# 1-Schematic_New_Project.net
KiCad netlist of a schematic drawn in EasyEDA
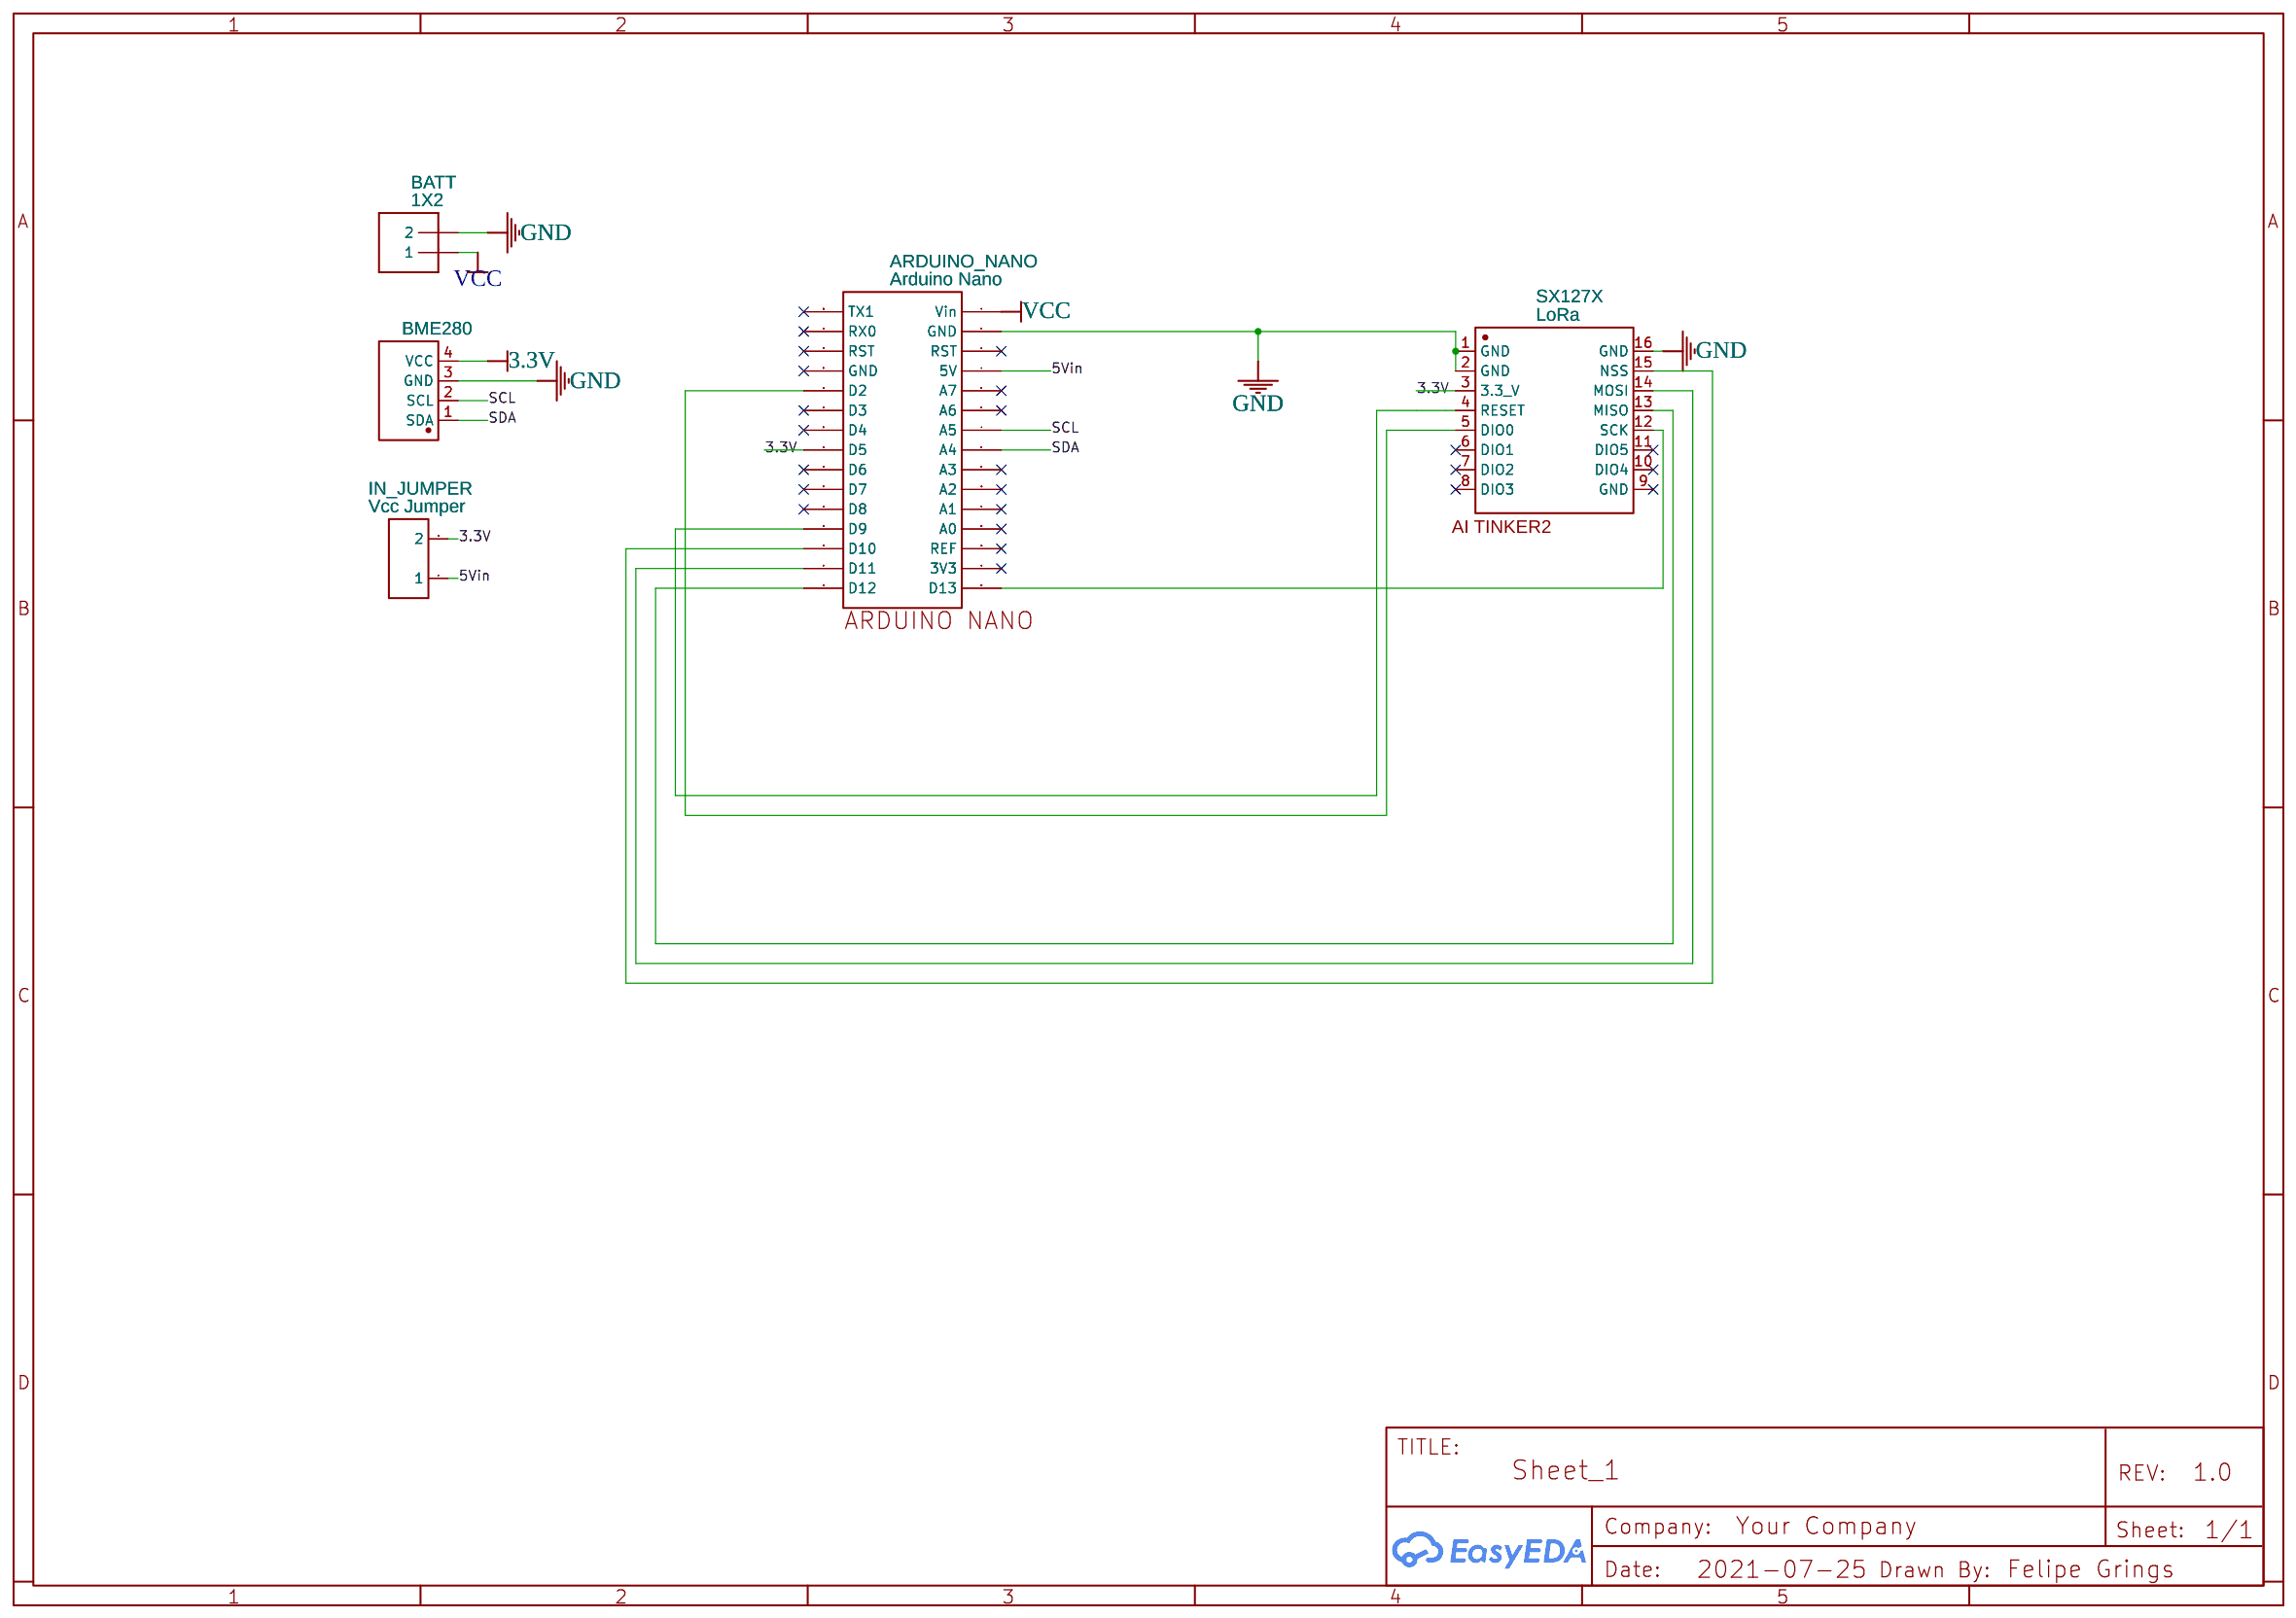
[diagram p0: schematic sheet]

(export (version "E")
  (design (tool "Eeschema 10.0.6"))
  (components
    (comp (ref "ARDUINO_NANO") (value "Arduino Nano") (libsource (lib "") (part "Arduino Nano")))
    (comp (ref "BATT") (value "1X2") (libsource (lib "") (part "1X2")))
    (comp (ref "IN_JUMPER")
      (value "Vcc Jumper")
      (fields (field (name "BOM_Manufacturer Part") "826629-2") (field (name "BOM_Supplier Part") "C86471"))
      (libsource (lib "") (part "Header-Male-2.54_1x2"))
    )
    (comp (ref "SDA") (value "BME280") (libsource (lib "") (part "GYBMEP")))
    (comp (ref "SX127X")
      (value "LoRa")
      (fields (field (name "BOM_Manufacturer Part") "SX1278") (field (name "BOM_Supplier Part") "C87473"))
      (libsource (lib "") (part "LoRa"))
    )
  )
  (nets
    (net (code "1") (name "/5Vin") (class "Default")
      (node (ref "ARDUINO_NANO") (pin "4") (pinfunction "5V_4") (pintype "unspecified"))
      (node (ref "IN_JUMPER") (pin "1") (pinfunction "1_1") (pintype "unspecified"))
    )
    (net (code "2") (name "/SCL") (class "Default")
      (node (ref "ARDUINO_NANO") (pin "7") (pinfunction "A5_7") (pintype "unspecified"))
      (node (ref "SDA") (pin "2") (pinfunction "SCL_2") (pintype "unspecified"))
    )
    (net (code "3") (name "/SDA") (class "Default")
      (node (ref "ARDUINO_NANO") (pin "8") (pinfunction "A4_8") (pintype "unspecified"))
      (node (ref "SDA") (pin "1") (pinfunction "SDA_1") (pintype "unspecified"))
    )
    (net (code "4") (name "3.3V") (class "Default")
      (node (ref "ARDUINO_NANO") (pin "23") (pinfunction "D5_23") (pintype "unspecified"))
      (node (ref "IN_JUMPER") (pin "2") (pinfunction "2_2") (pintype "unspecified"))
      (node (ref "SDA") (pin "4") (pinfunction "VCC_4") (pintype "unspecified"))
      (node (ref "SX127X") (pin "3") (pinfunction "3.3_V_3") (pintype "unspecified"))
    )
    (net (code "5") (name "GND") (class "Default")
      (node (ref "ARDUINO_NANO") (pin "2") (pinfunction "GND_2") (pintype "unspecified"))
      (node (ref "BATT") (pin "2") (pinfunction "2_2") (pintype "unspecified"))
      (node (ref "SDA") (pin "3") (pinfunction "GND_3") (pintype "unspecified"))
      (node (ref "SX127X") (pin "1") (pinfunction "GND_1") (pintype "unspecified"))
      (node (ref "SX127X") (pin "16") (pinfunction "GND_16") (pintype "unspecified"))
      (node (ref "SX127X") (pin "2") (pinfunction "GND_2") (pintype "unspecified"))
    )
    (net (code "6") (name "Net-(ARDUINO_NANO-D2)") (class "Default")
      (node (ref "ARDUINO_NANO") (pin "26") (pinfunction "D2_26") (pintype "unspecified"))
      (node (ref "SX127X") (pin "5") (pinfunction "DIO0_5") (pintype "unspecified"))
    )
    (net (code "7") (name "Net-(ARDUINO_NANO-D9)") (class "Default")
      (node (ref "ARDUINO_NANO") (pin "19") (pinfunction "D9_19") (pintype "unspecified"))
      (node (ref "SX127X") (pin "4") (pinfunction "RESET_4") (pintype "unspecified"))
    )
    (net (code "8") (name "Net-(ARDUINO_NANO-D10)") (class "Default")
      (node (ref "ARDUINO_NANO") (pin "18") (pinfunction "D10_18") (pintype "unspecified"))
      (node (ref "SX127X") (pin "15") (pinfunction "NSS_15") (pintype "unspecified"))
    )
    (net (code "9") (name "Net-(ARDUINO_NANO-D11)") (class "Default")
      (node (ref "ARDUINO_NANO") (pin "17") (pinfunction "D11_17") (pintype "unspecified"))
      (node (ref "SX127X") (pin "14") (pinfunction "MOSI_14") (pintype "unspecified"))
    )
    (net (code "10") (name "Net-(ARDUINO_NANO-D12)") (class "Default")
      (node (ref "ARDUINO_NANO") (pin "16") (pinfunction "D12_16") (pintype "unspecified"))
      (node (ref "SX127X") (pin "13") (pinfunction "MISO_13") (pintype "unspecified"))
    )
    (net (code "11") (name "Net-(ARDUINO_NANO-D13)") (class "Default")
      (node (ref "ARDUINO_NANO") (pin "15") (pinfunction "D13_15") (pintype "unspecified"))
      (node (ref "SX127X") (pin "12") (pinfunction "SCK_12") (pintype "unspecified"))
    )
    (net (code "12") (name "VCC") (class "Default")
      (node (ref "ARDUINO_NANO") (pin "1") (pinfunction "Vin_1") (pintype "unspecified"))
      (node (ref "BATT") (pin "1") (pinfunction "1_1") (pintype "unspecified"))
    )
    (net (code "13") (name "unconnected-(ARDUINO_NANO-3V3-Pad14)") (class "Default")
      (node (ref "ARDUINO_NANO") (pin "14") (pinfunction "3V3_14") (pintype "unspecified+no_connect"))
    )
    (net (code "14") (name "unconnected-(ARDUINO_NANO-A0-Pad12)") (class "Default")
      (node (ref "ARDUINO_NANO") (pin "12") (pinfunction "A0_12") (pintype "unspecified+no_connect"))
    )
    (net (code "15") (name "unconnected-(ARDUINO_NANO-A1-Pad11)") (class "Default")
      (node (ref "ARDUINO_NANO") (pin "11") (pinfunction "A1_11") (pintype "unspecified+no_connect"))
    )
    (net (code "16") (name "unconnected-(ARDUINO_NANO-A2-Pad10)") (class "Default")
      (node (ref "ARDUINO_NANO") (pin "10") (pinfunction "A2_10") (pintype "unspecified+no_connect"))
    )
    (net (code "17") (name "unconnected-(ARDUINO_NANO-A3-Pad9)") (class "Default")
      (node (ref "ARDUINO_NANO") (pin "9") (pinfunction "A3_9") (pintype "unspecified+no_connect"))
    )
    (net (code "18") (name "unconnected-(ARDUINO_NANO-A6-Pad6)") (class "Default")
      (node (ref "ARDUINO_NANO") (pin "6") (pinfunction "A6_6") (pintype "unspecified+no_connect"))
    )
    (net (code "19") (name "unconnected-(ARDUINO_NANO-A7-Pad5)") (class "Default")
      (node (ref "ARDUINO_NANO") (pin "5") (pinfunction "A7_5") (pintype "unspecified+no_connect"))
    )
    (net (code "20") (name "unconnected-(ARDUINO_NANO-D3-Pad25)") (class "Default")
      (node (ref "ARDUINO_NANO") (pin "25") (pinfunction "D3_25") (pintype "unspecified+no_connect"))
    )
    (net (code "21") (name "unconnected-(ARDUINO_NANO-D4-Pad24)") (class "Default")
      (node (ref "ARDUINO_NANO") (pin "24") (pinfunction "D4_24") (pintype "unspecified+no_connect"))
    )
    (net (code "22") (name "unconnected-(ARDUINO_NANO-D6-Pad22)") (class "Default")
      (node (ref "ARDUINO_NANO") (pin "22") (pinfunction "D6_22") (pintype "unspecified+no_connect"))
    )
    (net (code "23") (name "unconnected-(ARDUINO_NANO-D7-Pad21)") (class "Default")
      (node (ref "ARDUINO_NANO") (pin "21") (pinfunction "D7_21") (pintype "unspecified+no_connect"))
    )
    (net (code "24") (name "unconnected-(ARDUINO_NANO-D8-Pad20)") (class "Default")
      (node (ref "ARDUINO_NANO") (pin "20") (pinfunction "D8_20") (pintype "unspecified+no_connect"))
    )
    (net (code "25") (name "unconnected-(ARDUINO_NANO-GND-Pad27)") (class "Default")
      (node (ref "ARDUINO_NANO") (pin "27") (pinfunction "GND_27") (pintype "unspecified+no_connect"))
    )
    (net (code "26") (name "unconnected-(ARDUINO_NANO-REF-Pad13)") (class "Default")
      (node (ref "ARDUINO_NANO") (pin "13") (pinfunction "REF_13") (pintype "unspecified+no_connect"))
    )
    (net (code "27") (name "unconnected-(ARDUINO_NANO-RST-Pad3)") (class "Default")
      (node (ref "ARDUINO_NANO") (pin "3") (pinfunction "RST_3") (pintype "unspecified+no_connect"))
    )
    (net (code "28") (name "unconnected-(ARDUINO_NANO-RST-Pad28)") (class "Default")
      (node (ref "ARDUINO_NANO") (pin "28") (pinfunction "RST_28") (pintype "unspecified+no_connect"))
    )
    (net (code "29") (name "unconnected-(ARDUINO_NANO-RX0-Pad29)") (class "Default")
      (node (ref "ARDUINO_NANO") (pin "29") (pinfunction "RX0_29") (pintype "unspecified+no_connect"))
    )
    (net (code "30") (name "unconnected-(ARDUINO_NANO-TX1-Pad30)") (class "Default")
      (node (ref "ARDUINO_NANO") (pin "30") (pinfunction "TX1_30") (pintype "unspecified+no_connect"))
    )
    (net (code "31") (name "unconnected-(SX127X-DIO1-Pad6)") (class "Default")
      (node (ref "SX127X") (pin "6") (pinfunction "DIO1_6") (pintype "unspecified+no_connect"))
    )
    (net (code "32") (name "unconnected-(SX127X-DIO2-Pad7)") (class "Default")
      (node (ref "SX127X") (pin "7") (pinfunction "DIO2_7") (pintype "unspecified+no_connect"))
    )
    (net (code "33") (name "unconnected-(SX127X-DIO3-Pad8)") (class "Default")
      (node (ref "SX127X") (pin "8") (pinfunction "DIO3_8") (pintype "unspecified+no_connect"))
    )
    (net (code "34") (name "unconnected-(SX127X-DIO4-Pad10)") (class "Default")
      (node (ref "SX127X") (pin "10") (pinfunction "DIO4_10") (pintype "unspecified+no_connect"))
    )
    (net (code "35") (name "unconnected-(SX127X-DIO5-Pad11)") (class "Default")
      (node (ref "SX127X") (pin "11") (pinfunction "DIO5_11") (pintype "unspecified+no_connect"))
    )
    (net (code "36") (name "unconnected-(SX127X-GND-Pad9)") (class "Default")
      (node (ref "SX127X") (pin "9") (pinfunction "GND_9") (pintype "unspecified+no_connect"))
    )
  )
)
